# EAA690_RFID_Controller.net
KiCad netlist of a schematic drawn in EAGLE
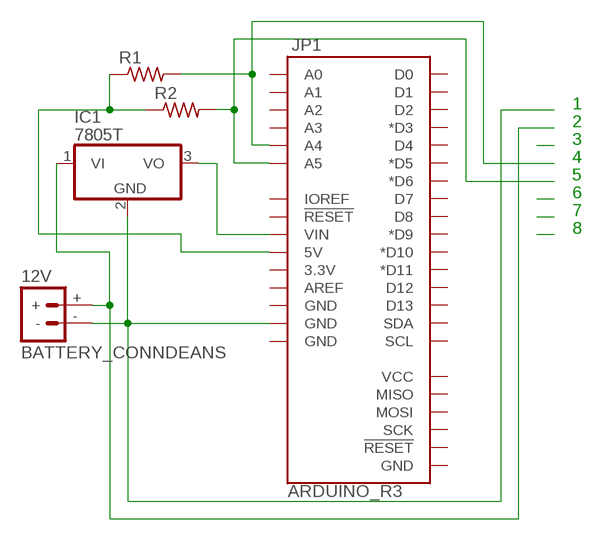
[diagram p0: schematic, sheet 1]

(export (version "E")
  (design (tool "Eeschema 10.0.6"))
  (components
    (comp (ref "12V")
      (value "BATTERY_CONNDEANS")
      (footprint "eagle-import:DEANS")
      (libsource (lib "eagle-import") (part "BATTERY_CONNDEANS"))
    )
    (comp (ref "IC1")
      (value "7805T")
      (footprint "eagle-import:TO220H")
      (libsource (lib "eagle-import") (part "78T05"))
    )
    (comp (ref "JP1")
      (value "ARDUINO_R3")
      (footprint "eagle-import:ARDUINO_R3")
      (libsource (lib "eagle-import") (part "ARDUINO_R3"))
    )
    (comp (ref "R1")
      (value "R-US_0204/5")
      (footprint "eagle-import:0204_5")
      (libsource (lib "eagle-import") (part "R-US_0204/5"))
    )
    (comp (ref "R2")
      (value "R-US_0204/5")
      (footprint "eagle-import:0204_5")
      (libsource (lib "eagle-import") (part "R-US_0204/5"))
    )
  )
  (nets
    (net (code "1") (name "Net-(IC1-GND)") (class "Default")
      (node (ref "12V") (pin "-") (pinfunction "-_-") (pintype "passive"))
      (node (ref "IC1") (pin "2") (pinfunction "GND_2") (pintype "passive"))
      (node (ref "JP1") (pin "GND@3") (pinfunction "GND_GND@3") (pintype "bidirectional"))
    )
    (net (code "2") (name "Net-(IC1-VI)") (class "Default")
      (node (ref "12V") (pin "+") (pinfunction "+_+") (pintype "passive"))
      (node (ref "IC1") (pin "1") (pinfunction "VI_1") (pintype "input"))
    )
    (net (code "3") (name "Net-(IC1-VO)") (class "Default")
      (node (ref "IC1") (pin "3") (pinfunction "VO_3") (pintype "passive"))
      (node (ref "JP1") (pin "VIN") (pinfunction "VIN_VIN") (pintype "bidirectional"))
    )
    (net (code "4") (name "Net-(JP1-Pad5V)") (class "Default")
      (node (ref "JP1") (pin "5V") (pinfunction "5V_5V") (pintype "bidirectional"))
      (node (ref "R1") (pin "1") (pinfunction "1_1") (pintype "passive"))
      (node (ref "R2") (pin "1") (pinfunction "1_1") (pintype "passive"))
    )
    (net (code "5") (name "Net-(JP1-PadA4)") (class "Default")
      (node (ref "JP1") (pin "A4") (pinfunction "A4_A4") (pintype "bidirectional"))
      (node (ref "R1") (pin "2") (pinfunction "2_2") (pintype "passive"))
    )
    (net (code "6") (name "Net-(JP1-PadA5)") (class "Default")
      (node (ref "JP1") (pin "A5") (pinfunction "A5_A5") (pintype "bidirectional"))
      (node (ref "R2") (pin "2") (pinfunction "2_2") (pintype "passive"))
    )
    (net (code "7") (name "unconnected-(JP1-*D3-PadD3)") (class "Default")
      (node (ref "JP1") (pin "D3") (pinfunction "*D3_D3") (pintype "bidirectional"))
    )
    (net (code "8") (name "unconnected-(JP1-*D5-PadD5)") (class "Default")
      (node (ref "JP1") (pin "D5") (pinfunction "*D5_D5") (pintype "bidirectional"))
    )
    (net (code "9") (name "unconnected-(JP1-*D6-PadD6)") (class "Default")
      (node (ref "JP1") (pin "D6") (pinfunction "*D6_D6") (pintype "bidirectional"))
    )
    (net (code "10") (name "unconnected-(JP1-*D9-PadD9)") (class "Default")
      (node (ref "JP1") (pin "D9") (pinfunction "*D9_D9") (pintype "bidirectional"))
    )
    (net (code "11") (name "unconnected-(JP1-*D10-PadD10)") (class "Default")
      (node (ref "JP1") (pin "D10") (pinfunction "*D10_D10") (pintype "bidirectional"))
    )
    (net (code "12") (name "unconnected-(JP1-*D11-PadD11)") (class "Default")
      (node (ref "JP1") (pin "D11") (pinfunction "*D11_D11") (pintype "bidirectional"))
    )
    (net (code "13") (name "unconnected-(JP1-GND-PadGND@1)") (class "Default")
      (node (ref "JP1") (pin "GND@1") (pinfunction "GND_GND@1") (pintype "bidirectional"))
    )
    (net (code "14") (name "unconnected-(JP1-GND-PadGND@2)") (class "Default")
      (node (ref "JP1") (pin "GND@2") (pinfunction "GND_GND@2") (pintype "bidirectional"))
    )
    (net (code "15") (name "unconnected-(JP1-GND-PadGND@4)") (class "Default")
      (node (ref "JP1") (pin "GND@4") (pinfunction "GND_GND@4") (pintype "bidirectional"))
    )
    (net (code "16") (name "unconnected-(JP1-Pad3.3V)") (class "Default")
      (node (ref "JP1") (pin "3.3V") (pinfunction "3.3V_3.3V") (pintype "bidirectional"))
    )
    (net (code "17") (name "unconnected-(JP1-PadA0)") (class "Default")
      (node (ref "JP1") (pin "A0") (pinfunction "A0_A0") (pintype "bidirectional"))
    )
    (net (code "18") (name "unconnected-(JP1-PadA1)") (class "Default")
      (node (ref "JP1") (pin "A1") (pinfunction "A1_A1") (pintype "bidirectional"))
    )
    (net (code "19") (name "unconnected-(JP1-PadA2)") (class "Default")
      (node (ref "JP1") (pin "A2") (pinfunction "A2_A2") (pintype "bidirectional"))
    )
    (net (code "20") (name "unconnected-(JP1-PadA3)") (class "Default")
      (node (ref "JP1") (pin "A3") (pinfunction "A3_A3") (pintype "bidirectional"))
    )
    (net (code "21") (name "unconnected-(JP1-PadAREF)") (class "Default")
      (node (ref "JP1") (pin "AREF") (pinfunction "AREF_AREF") (pintype "bidirectional"))
    )
    (net (code "22") (name "unconnected-(JP1-PadD0)") (class "Default")
      (node (ref "JP1") (pin "D0") (pinfunction "D0_D0") (pintype "bidirectional"))
    )
    (net (code "23") (name "unconnected-(JP1-PadD1)") (class "Default")
      (node (ref "JP1") (pin "D1") (pinfunction "D1_D1") (pintype "bidirectional"))
    )
    (net (code "24") (name "unconnected-(JP1-PadD2)") (class "Default")
      (node (ref "JP1") (pin "D2") (pinfunction "D2_D2") (pintype "bidirectional"))
    )
    (net (code "25") (name "unconnected-(JP1-PadD4)") (class "Default")
      (node (ref "JP1") (pin "D4") (pinfunction "D4_D4") (pintype "bidirectional"))
    )
    (net (code "26") (name "unconnected-(JP1-PadD7)") (class "Default")
      (node (ref "JP1") (pin "D7") (pinfunction "D7_D7") (pintype "bidirectional"))
    )
    (net (code "27") (name "unconnected-(JP1-PadD8)") (class "Default")
      (node (ref "JP1") (pin "D8") (pinfunction "D8_D8") (pintype "bidirectional"))
    )
    (net (code "28") (name "unconnected-(JP1-PadD12)") (class "Default")
      (node (ref "JP1") (pin "D12") (pinfunction "D12_D12") (pintype "bidirectional"))
    )
    (net (code "29") (name "unconnected-(JP1-PadD13)") (class "Default")
      (node (ref "JP1") (pin "D13") (pinfunction "D13_D13") (pintype "bidirectional"))
    )
    (net (code "30") (name "unconnected-(JP1-PadIOREF)") (class "Default")
      (node (ref "JP1") (pin "IOREF") (pinfunction "IOREF_IOREF") (pintype "bidirectional"))
    )
    (net (code "31") (name "unconnected-(JP1-PadMISO)") (class "Default")
      (node (ref "JP1") (pin "MISO") (pinfunction "MISO_MISO") (pintype "bidirectional"))
    )
    (net (code "32") (name "unconnected-(JP1-PadMOSI)") (class "Default")
      (node (ref "JP1") (pin "MOSI") (pinfunction "MOSI_MOSI") (pintype "bidirectional"))
    )
    (net (code "33") (name "unconnected-(JP1-PadSCK)") (class "Default")
      (node (ref "JP1") (pin "SCK") (pinfunction "SCK_SCK") (pintype "bidirectional"))
    )
    (net (code "34") (name "unconnected-(JP1-PadSCL)") (class "Default")
      (node (ref "JP1") (pin "SCL") (pinfunction "SCL_SCL") (pintype "bidirectional"))
    )
    (net (code "35") (name "unconnected-(JP1-PadSDA)") (class "Default")
      (node (ref "JP1") (pin "SDA") (pinfunction "SDA_SDA") (pintype "bidirectional"))
    )
    (net (code "36") (name "unconnected-(JP1-PadVCC)") (class "Default")
      (node (ref "JP1") (pin "VCC") (pinfunction "VCC_VCC") (pintype "bidirectional"))
    )
    (net (code "37") (name "unconnected-(JP1-~{RESET}-PadRESET@1)") (class "Default")
      (node (ref "JP1") (pin "RESET@1") (pinfunction "~{RESET}_RESET@1") (pintype "bidirectional"))
    )
    (net (code "38") (name "unconnected-(JP1-~{RESET}-PadRESET@2)") (class "Default")
      (node (ref "JP1") (pin "RESET@2") (pinfunction "~{RESET}_RESET@2") (pintype "bidirectional"))
    )
  )
)
